# Sheet1.net
KiCad netlist of a schematic drawn in Altium Designer
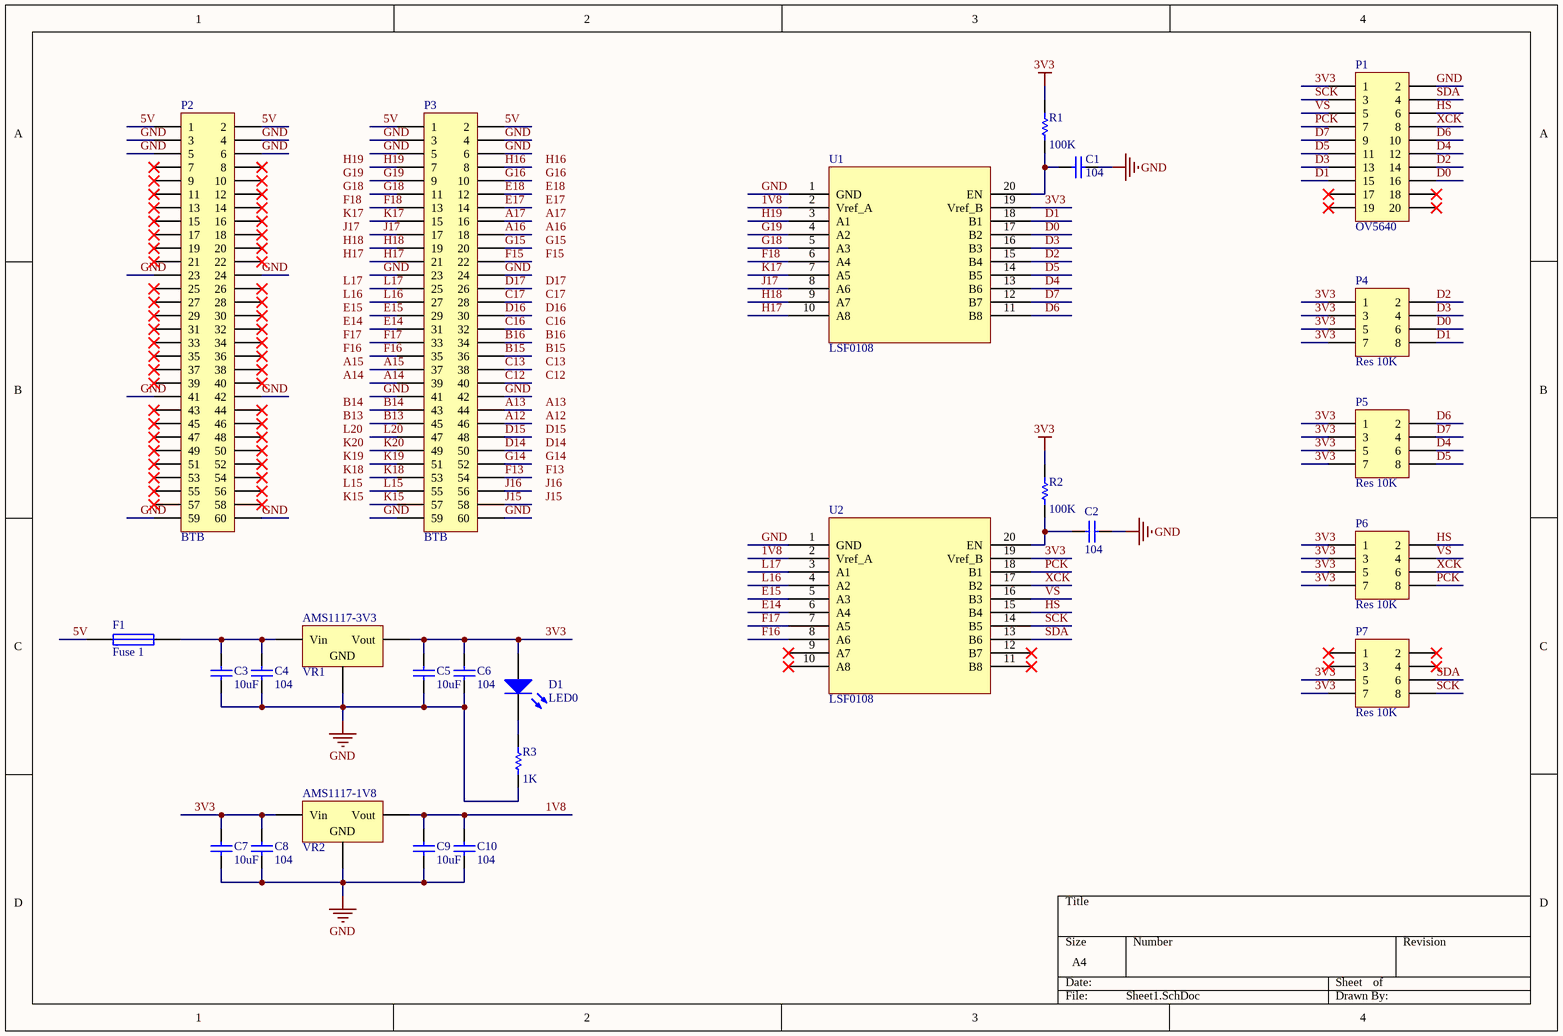
[diagram p0: Sheet1.SchDoc]

(export (version "E")
  (design (tool "Eeschema 10.0.6"))
  (components
    (comp (ref "C1")
      (value "104")
      (footprint "R0805")
      (description "Capacitor")
      (fields (field (name "Comment") "Cap") (field (name "PUBLISHER") "Altium Limited"))
      (libsource (lib "Miscellaneous Devices") (part "Cap"))
    )
    (comp (ref "C2")
      (value "104")
      (footprint "R0805")
      (description "Capacitor")
      (fields (field (name "Comment") "Cap") (field (name "PUBLISHER") "Altium Limited"))
      (libsource (lib "Miscellaneous Devices") (part "Cap"))
    )
    (comp (ref "C3")
      (value "10uF")
      (footprint "R0805")
      (description "Capacitor")
      (fields (field (name "Comment") "Cap") (field (name "PUBLISHER") "Altium Limited"))
      (libsource (lib "Miscellaneous Devices") (part "Cap"))
    )
    (comp (ref "C4")
      (value "104")
      (footprint "R0805")
      (description "Capacitor")
      (fields (field (name "Comment") "Cap") (field (name "PUBLISHER") "Altium Limited"))
      (libsource (lib "Miscellaneous Devices") (part "Cap"))
    )
    (comp (ref "C5")
      (value "10uF")
      (footprint "R0805")
      (description "Capacitor")
      (fields (field (name "Comment") "Cap") (field (name "PUBLISHER") "Altium Limited"))
      (libsource (lib "Miscellaneous Devices") (part "Cap"))
    )
    (comp (ref "C6")
      (value "104")
      (footprint "R0805")
      (description "Capacitor")
      (fields (field (name "Comment") "Cap") (field (name "PUBLISHER") "Altium Limited"))
      (libsource (lib "Miscellaneous Devices") (part "Cap"))
    )
    (comp (ref "C7")
      (value "10uF")
      (footprint "R0805")
      (description "Capacitor")
      (fields (field (name "Comment") "Cap") (field (name "PUBLISHER") "Altium Limited"))
      (libsource (lib "Miscellaneous Devices") (part "Cap"))
    )
    (comp (ref "C8")
      (value "104")
      (footprint "R0805")
      (description "Capacitor")
      (fields (field (name "Comment") "Cap") (field (name "PUBLISHER") "Altium Limited"))
      (libsource (lib "Miscellaneous Devices") (part "Cap"))
    )
    (comp (ref "C9")
      (value "10uF")
      (footprint "R0805")
      (description "Capacitor")
      (fields (field (name "Comment") "Cap") (field (name "PUBLISHER") "Altium Limited"))
      (libsource (lib "Miscellaneous Devices") (part "Cap"))
    )
    (comp (ref "C10")
      (value "104")
      (footprint "R0805")
      (description "Capacitor")
      (fields (field (name "Comment") "Cap") (field (name "PUBLISHER") "Altium Limited"))
      (libsource (lib "Miscellaneous Devices") (part "Cap"))
    )
    (comp (ref "D1")
      (value "LED0")
      (footprint "LED0805红")
      (description "Typical INFRARED GaAs LED")
      (fields (field (name "PUBLISHER") "Altium Limited"))
      (libsource (lib "Miscellaneous Devices") (part "LED0"))
    )
    (comp (ref "F1")
      (value "Fuse 1")
      (footprint "R1206")
      (description "Fuse")
      (fields (field (name "PUBLISHER") "Altium Limited"))
      (libsource (lib "Miscellaneous Devices") (part "Fuse 1"))
    )
    (comp (ref "P1")
      (value "OV5640")
      (footprint "HDR2X10")
      (description "Header, 10-Pin, Dual row")
      (fields (field (name "PUBLISHER") "Altium Limited"))
      (libsource (lib "Miscellaneous Connectors") (part "Header 10X2"))
    )
    (comp (ref "P2")
      (value "BTB")
      (footprint "BTBCON_0.8mm_60P")
      (description "Header, 30-Pin, Dual row")
      (fields (field (name "PUBLISHER") "Altium Limited"))
      (libsource (lib "Miscellaneous Connectors") (part "Header 30X2"))
    )
    (comp (ref "P3")
      (value "BTB")
      (footprint "BTBCON_0.8mm_60P")
      (description "Header, 30-Pin, Dual row")
      (fields (field (name "PUBLISHER") "Altium Limited"))
      (libsource (lib "Miscellaneous Connectors") (part "Header 30X2"))
    )
    (comp (ref "P4")
      (value "Res 10K")
      (footprint "排阻(4位贴片)")
      (description "Header, 4-Pin, Dual row")
      (fields (field (name "PUBLISHER") "Altium Limited"))
      (libsource (lib "Miscellaneous Connectors") (part "Header 4X2"))
    )
    (comp (ref "P5")
      (value "Res 10K")
      (footprint "排阻(4位贴片)")
      (description "Header, 4-Pin, Dual row")
      (fields (field (name "PUBLISHER") "Altium Limited"))
      (libsource (lib "Miscellaneous Connectors") (part "Header 4X2"))
    )
    (comp (ref "P6")
      (value "Res 10K")
      (footprint "排阻(4位贴片)")
      (description "Header, 4-Pin, Dual row")
      (fields (field (name "PUBLISHER") "Altium Limited"))
      (libsource (lib "Miscellaneous Connectors") (part "Header 4X2"))
    )
    (comp (ref "P7")
      (value "Res 10K")
      (footprint "排阻(4位贴片)")
      (description "Header, 4-Pin, Dual row")
      (fields (field (name "PUBLISHER") "Altium Limited"))
      (libsource (lib "Miscellaneous Connectors") (part "Header 4X2"))
    )
    (comp (ref "R1")
      (value "100K")
      (footprint "R0805")
      (description "Semiconductor Resistor")
      (fields (field (name "Comment") "Res Semi") (field (name "PUBLISHER") "Altium Limited"))
      (libsource (lib "Miscellaneous Devices") (part "Res Semi"))
    )
    (comp (ref "R2")
      (value "100K")
      (footprint "R0805")
      (description "Semiconductor Resistor")
      (fields (field (name "Comment") "Res Semi") (field (name "PUBLISHER") "Altium Limited"))
      (libsource (lib "Miscellaneous Devices") (part "Res Semi"))
    )
    (comp (ref "R3")
      (value "1K")
      (footprint "R0805")
      (description "Resistor")
      (fields (field (name "Comment") "Res1") (field (name "PUBLISHER") "Altium Limited"))
      (libsource (lib "Miscellaneous Devices") (part "Res1"))
    )
    (comp (ref "U1")
      (value "LSF0108")
      (footprint "TSSOP20 74lvc245")
      (libsource (lib "LSF0108") (part "LSF0108"))
    )
    (comp (ref "U2")
      (value "LSF0108")
      (footprint "TSSOP20 74lvc245")
      (libsource (lib "LSF0108") (part "LSF0108"))
    )
    (comp (ref "VR1")
      (value "AMS1117-3V3")
      (footprint "SOT-223")
      (description "Voltage Regulator")
      (fields (field (name "PUBLISHER") "Altium Limited"))
      (libsource (lib "Miscellaneous Devices") (part "Volt Reg"))
    )
    (comp (ref "VR2")
      (value "AMS1117-1V8")
      (footprint "SOT-223")
      (description "Voltage Regulator")
      (fields (field (name "PUBLISHER") "Altium Limited"))
      (libsource (lib "Miscellaneous Devices") (part "Volt Reg"))
    )
  )
  (nets
    (net (code "1") (name "/1V8") (class "Default")
      (node (ref "C10") (pin "2") (pinfunction "2_2") (pintype "passive"))
      (node (ref "C9") (pin "2") (pinfunction "2_2") (pintype "passive"))
      (node (ref "U1") (pin "2") (pinfunction "Vref_A_2") (pintype "passive"))
      (node (ref "U2") (pin "2") (pinfunction "Vref_A_2") (pintype "passive"))
      (node (ref "VR2") (pin "2") (pinfunction "Vout_2") (pintype "passive"))
    )
    (net (code "2") (name "/5V") (class "Default")
      (node (ref "F1") (pin "1") (pinfunction "1_1") (pintype "passive"))
      (node (ref "P2") (pin "1") (pinfunction "1_1") (pintype "passive"))
      (node (ref "P2") (pin "2") (pinfunction "2_2") (pintype "passive"))
      (node (ref "P3") (pin "1") (pinfunction "1_1") (pintype "passive"))
      (node (ref "P3") (pin "2") (pinfunction "2_2") (pintype "passive"))
    )
    (net (code "3") (name "/A12") (class "Default")
      (node (ref "P3") (pin "46") (pinfunction "46_46") (pintype "passive"))
    )
    (net (code "4") (name "/A13") (class "Default")
      (node (ref "P3") (pin "44") (pinfunction "44_44") (pintype "passive"))
    )
    (net (code "5") (name "/A14") (class "Default")
      (node (ref "P3") (pin "39") (pinfunction "39_39") (pintype "passive"))
    )
    (net (code "6") (name "/A15") (class "Default")
      (node (ref "P3") (pin "37") (pinfunction "37_37") (pintype "passive"))
    )
    (net (code "7") (name "/A16") (class "Default")
      (node (ref "P3") (pin "18") (pinfunction "18_18") (pintype "passive"))
    )
    (net (code "8") (name "/A17") (class "Default")
      (node (ref "P3") (pin "16") (pinfunction "16_16") (pintype "passive"))
    )
    (net (code "9") (name "/B13") (class "Default")
      (node (ref "P3") (pin "45") (pinfunction "45_45") (pintype "passive"))
    )
    (net (code "10") (name "/B14") (class "Default")
      (node (ref "P3") (pin "43") (pinfunction "43_43") (pintype "passive"))
    )
    (net (code "11") (name "/B15") (class "Default")
      (node (ref "P3") (pin "36") (pinfunction "36_36") (pintype "passive"))
    )
    (net (code "12") (name "/B16") (class "Default")
      (node (ref "P3") (pin "34") (pinfunction "34_34") (pintype "passive"))
    )
    (net (code "13") (name "/C12") (class "Default")
      (node (ref "P3") (pin "40") (pinfunction "40_40") (pintype "passive"))
    )
    (net (code "14") (name "/C13") (class "Default")
      (node (ref "P3") (pin "38") (pinfunction "38_38") (pintype "passive"))
    )
    (net (code "15") (name "/C16") (class "Default")
      (node (ref "P3") (pin "32") (pinfunction "32_32") (pintype "passive"))
    )
    (net (code "16") (name "/C17") (class "Default")
      (node (ref "P3") (pin "28") (pinfunction "28_28") (pintype "passive"))
    )
    (net (code "17") (name "/D0") (class "Default")
      (node (ref "P1") (pin "16") (pinfunction "16_16") (pintype "passive"))
      (node (ref "P4") (pin "6") (pinfunction "6_6") (pintype "passive"))
      (node (ref "U1") (pin "17") (pinfunction "B2_17") (pintype "passive"))
    )
    (net (code "18") (name "/D1") (class "Default")
      (node (ref "P1") (pin "15") (pinfunction "15_15") (pintype "passive"))
      (node (ref "P4") (pin "8") (pinfunction "8_8") (pintype "passive"))
      (node (ref "U1") (pin "18") (pinfunction "B1_18") (pintype "passive"))
    )
    (net (code "19") (name "/D2") (class "Default")
      (node (ref "P1") (pin "14") (pinfunction "14_14") (pintype "passive"))
      (node (ref "P4") (pin "2") (pinfunction "2_2") (pintype "passive"))
      (node (ref "U1") (pin "15") (pinfunction "B4_15") (pintype "passive"))
    )
    (net (code "20") (name "/D3") (class "Default")
      (node (ref "P1") (pin "13") (pinfunction "13_13") (pintype "passive"))
      (node (ref "P4") (pin "4") (pinfunction "4_4") (pintype "passive"))
      (node (ref "U1") (pin "16") (pinfunction "B3_16") (pintype "passive"))
    )
    (net (code "21") (name "/D4") (class "Default")
      (node (ref "P1") (pin "12") (pinfunction "12_12") (pintype "passive"))
      (node (ref "P5") (pin "6") (pinfunction "6_6") (pintype "passive"))
      (node (ref "U1") (pin "13") (pinfunction "B6_13") (pintype "passive"))
    )
    (net (code "22") (name "/D5") (class "Default")
      (node (ref "P1") (pin "11") (pinfunction "11_11") (pintype "passive"))
      (node (ref "P5") (pin "8") (pinfunction "8_8") (pintype "passive"))
      (node (ref "U1") (pin "14") (pinfunction "B5_14") (pintype "passive"))
    )
    (net (code "23") (name "/D6") (class "Default")
      (node (ref "P1") (pin "10") (pinfunction "10_10") (pintype "passive"))
      (node (ref "P5") (pin "2") (pinfunction "2_2") (pintype "passive"))
      (node (ref "U1") (pin "11") (pinfunction "B8_11") (pintype "passive"))
    )
    (net (code "24") (name "/D7") (class "Default")
      (node (ref "P1") (pin "9") (pinfunction "9_9") (pintype "passive"))
      (node (ref "P5") (pin "4") (pinfunction "4_4") (pintype "passive"))
      (node (ref "U1") (pin "12") (pinfunction "B7_12") (pintype "passive"))
    )
    (net (code "25") (name "/D14") (class "Default")
      (node (ref "P3") (pin "50") (pinfunction "50_50") (pintype "passive"))
    )
    (net (code "26") (name "/D15") (class "Default")
      (node (ref "P3") (pin "48") (pinfunction "48_48") (pintype "passive"))
    )
    (net (code "27") (name "/D16") (class "Default")
      (node (ref "P3") (pin "30") (pinfunction "30_30") (pintype "passive"))
    )
    (net (code "28") (name "/D17") (class "Default")
      (node (ref "P3") (pin "26") (pinfunction "26_26") (pintype "passive"))
    )
    (net (code "29") (name "/E14") (class "Default")
      (node (ref "P3") (pin "31") (pinfunction "31_31") (pintype "passive"))
      (node (ref "U2") (pin "6") (pinfunction "A4_6") (pintype "passive"))
    )
    (net (code "30") (name "/E15") (class "Default")
      (node (ref "P3") (pin "29") (pinfunction "29_29") (pintype "passive"))
      (node (ref "U2") (pin "5") (pinfunction "A3_5") (pintype "passive"))
    )
    (net (code "31") (name "/E17") (class "Default")
      (node (ref "P3") (pin "14") (pinfunction "14_14") (pintype "passive"))
    )
    (net (code "32") (name "/E18") (class "Default")
      (node (ref "P3") (pin "12") (pinfunction "12_12") (pintype "passive"))
    )
    (net (code "33") (name "/F13") (class "Default")
      (node (ref "P3") (pin "54") (pinfunction "54_54") (pintype "passive"))
    )
    (net (code "34") (name "/F15") (class "Default")
      (node (ref "P3") (pin "22") (pinfunction "22_22") (pintype "passive"))
    )
    (net (code "35") (name "/F16") (class "Default")
      (node (ref "P3") (pin "35") (pinfunction "35_35") (pintype "passive"))
      (node (ref "U2") (pin "8") (pinfunction "A6_8") (pintype "passive"))
    )
    (net (code "36") (name "/F17") (class "Default")
      (node (ref "P3") (pin "33") (pinfunction "33_33") (pintype "passive"))
      (node (ref "U2") (pin "7") (pinfunction "A5_7") (pintype "passive"))
    )
    (net (code "37") (name "/F18") (class "Default")
      (node (ref "P3") (pin "13") (pinfunction "13_13") (pintype "passive"))
      (node (ref "U1") (pin "6") (pinfunction "A4_6") (pintype "passive"))
    )
    (net (code "38") (name "/G14") (class "Default")
      (node (ref "P3") (pin "52") (pinfunction "52_52") (pintype "passive"))
    )
    (net (code "39") (name "/G15") (class "Default")
      (node (ref "P3") (pin "20") (pinfunction "20_20") (pintype "passive"))
    )
    (net (code "40") (name "/G16") (class "Default")
      (node (ref "P3") (pin "10") (pinfunction "10_10") (pintype "passive"))
    )
    (net (code "41") (name "/G18") (class "Default")
      (node (ref "P3") (pin "11") (pinfunction "11_11") (pintype "passive"))
      (node (ref "U1") (pin "5") (pinfunction "A3_5") (pintype "passive"))
    )
    (net (code "42") (name "/G19") (class "Default")
      (node (ref "P3") (pin "9") (pinfunction "9_9") (pintype "passive"))
      (node (ref "U1") (pin "4") (pinfunction "A2_4") (pintype "passive"))
    )
    (net (code "43") (name "/H16") (class "Default")
      (node (ref "P3") (pin "8") (pinfunction "8_8") (pintype "passive"))
    )
    (net (code "44") (name "/H17") (class "Default")
      (node (ref "P3") (pin "21") (pinfunction "21_21") (pintype "passive"))
      (node (ref "U1") (pin "10") (pinfunction "A8_10") (pintype "passive"))
    )
    (net (code "45") (name "/H18") (class "Default")
      (node (ref "P3") (pin "19") (pinfunction "19_19") (pintype "passive"))
      (node (ref "U1") (pin "9") (pinfunction "A7_9") (pintype "passive"))
    )
    (net (code "46") (name "/H19") (class "Default")
      (node (ref "P3") (pin "7") (pinfunction "7_7") (pintype "passive"))
      (node (ref "U1") (pin "3") (pinfunction "A1_3") (pintype "passive"))
    )
    (net (code "47") (name "/HS") (class "Default")
      (node (ref "P1") (pin "6") (pinfunction "6_6") (pintype "passive"))
      (node (ref "P6") (pin "2") (pinfunction "2_2") (pintype "passive"))
      (node (ref "U2") (pin "15") (pinfunction "B4_15") (pintype "passive"))
    )
    (net (code "48") (name "/J15") (class "Default")
      (node (ref "P3") (pin "58") (pinfunction "58_58") (pintype "passive"))
    )
    (net (code "49") (name "/J16") (class "Default")
      (node (ref "P3") (pin "56") (pinfunction "56_56") (pintype "passive"))
    )
    (net (code "50") (name "/J17") (class "Default")
      (node (ref "P3") (pin "17") (pinfunction "17_17") (pintype "passive"))
      (node (ref "U1") (pin "8") (pinfunction "A6_8") (pintype "passive"))
    )
    (net (code "51") (name "/K15") (class "Default")
      (node (ref "P3") (pin "57") (pinfunction "57_57") (pintype "passive"))
    )
    (net (code "52") (name "/K17") (class "Default")
      (node (ref "P3") (pin "15") (pinfunction "15_15") (pintype "passive"))
      (node (ref "U1") (pin "7") (pinfunction "A5_7") (pintype "passive"))
    )
    (net (code "53") (name "/K18") (class "Default")
      (node (ref "P3") (pin "53") (pinfunction "53_53") (pintype "passive"))
    )
    (net (code "54") (name "/K19") (class "Default")
      (node (ref "P3") (pin "51") (pinfunction "51_51") (pintype "passive"))
    )
    (net (code "55") (name "/K20") (class "Default")
      (node (ref "P3") (pin "49") (pinfunction "49_49") (pintype "passive"))
    )
    (net (code "56") (name "/L15") (class "Default")
      (node (ref "P3") (pin "55") (pinfunction "55_55") (pintype "passive"))
    )
    (net (code "57") (name "/L16") (class "Default")
      (node (ref "P3") (pin "27") (pinfunction "27_27") (pintype "passive"))
      (node (ref "U2") (pin "4") (pinfunction "A2_4") (pintype "passive"))
    )
    (net (code "58") (name "/L17") (class "Default")
      (node (ref "P3") (pin "25") (pinfunction "25_25") (pintype "passive"))
      (node (ref "U2") (pin "3") (pinfunction "A1_3") (pintype "passive"))
    )
    (net (code "59") (name "/L20") (class "Default")
      (node (ref "P3") (pin "47") (pinfunction "47_47") (pintype "passive"))
    )
    (net (code "60") (name "/PCK") (class "Default")
      (node (ref "P1") (pin "7") (pinfunction "7_7") (pintype "passive"))
      (node (ref "P6") (pin "8") (pinfunction "8_8") (pintype "passive"))
      (node (ref "U2") (pin "18") (pinfunction "B1_18") (pintype "passive"))
    )
    (net (code "61") (name "/SCK") (class "Default")
      (node (ref "P1") (pin "3") (pinfunction "3_3") (pintype "passive"))
      (node (ref "P7") (pin "8") (pinfunction "8_8") (pintype "passive"))
      (node (ref "U2") (pin "14") (pinfunction "B5_14") (pintype "passive"))
    )
    (net (code "62") (name "/SDA") (class "Default")
      (node (ref "P1") (pin "4") (pinfunction "4_4") (pintype "passive"))
      (node (ref "P7") (pin "6") (pinfunction "6_6") (pintype "passive"))
      (node (ref "U2") (pin "13") (pinfunction "B6_13") (pintype "passive"))
    )
    (net (code "63") (name "/VS") (class "Default")
      (node (ref "P1") (pin "5") (pinfunction "5_5") (pintype "passive"))
      (node (ref "P6") (pin "4") (pinfunction "4_4") (pintype "passive"))
      (node (ref "U2") (pin "16") (pinfunction "B3_16") (pintype "passive"))
    )
    (net (code "64") (name "/XCK") (class "Default")
      (node (ref "P1") (pin "8") (pinfunction "8_8") (pintype "passive"))
      (node (ref "P6") (pin "6") (pinfunction "6_6") (pintype "passive"))
      (node (ref "U2") (pin "17") (pinfunction "B2_17") (pintype "passive"))
    )
    (net (code "65") (name "3V3") (class "Default")
      (node (ref "C5") (pin "2") (pinfunction "2_2") (pintype "passive"))
      (node (ref "C6") (pin "2") (pinfunction "2_2") (pintype "passive"))
      (node (ref "C7") (pin "2") (pinfunction "2_2") (pintype "passive"))
      (node (ref "C8") (pin "2") (pinfunction "2_2") (pintype "passive"))
      (node (ref "D1") (pin "1") (pinfunction "A_1") (pintype "passive"))
      (node (ref "P1") (pin "1") (pinfunction "1_1") (pintype "passive"))
      (node (ref "P4") (pin "1") (pinfunction "1_1") (pintype "passive"))
      (node (ref "P4") (pin "3") (pinfunction "3_3") (pintype "passive"))
      (node (ref "P4") (pin "5") (pinfunction "5_5") (pintype "passive"))
      (node (ref "P4") (pin "7") (pinfunction "7_7") (pintype "passive"))
      (node (ref "P5") (pin "1") (pinfunction "1_1") (pintype "passive"))
      (node (ref "P5") (pin "3") (pinfunction "3_3") (pintype "passive"))
      (node (ref "P5") (pin "5") (pinfunction "5_5") (pintype "passive"))
      (node (ref "P5") (pin "7") (pinfunction "7_7") (pintype "passive"))
      (node (ref "P6") (pin "1") (pinfunction "1_1") (pintype "passive"))
      (node (ref "P6") (pin "3") (pinfunction "3_3") (pintype "passive"))
      (node (ref "P6") (pin "5") (pinfunction "5_5") (pintype "passive"))
      (node (ref "P6") (pin "7") (pinfunction "7_7") (pintype "passive"))
      (node (ref "P7") (pin "5") (pinfunction "5_5") (pintype "passive"))
      (node (ref "P7") (pin "7") (pinfunction "7_7") (pintype "passive"))
      (node (ref "R1") (pin "2") (pinfunction "2_2") (pintype "passive"))
      (node (ref "R2") (pin "2") (pinfunction "2_2") (pintype "passive"))
      (node (ref "U1") (pin "19") (pinfunction "Vref_B_19") (pintype "passive"))
      (node (ref "U2") (pin "19") (pinfunction "Vref_B_19") (pintype "passive"))
      (node (ref "VR1") (pin "2") (pinfunction "Vout_2") (pintype "passive"))
      (node (ref "VR2") (pin "3") (pinfunction "Vin_3") (pintype "passive"))
    )
    (net (code "66") (name "GND") (class "Default")
      (node (ref "C1") (pin "2") (pinfunction "2_2") (pintype "passive"))
      (node (ref "C10") (pin "1") (pinfunction "1_1") (pintype "passive"))
      (node (ref "C2") (pin "1") (pinfunction "1_1") (pintype "passive"))
      (node (ref "C3") (pin "1") (pinfunction "1_1") (pintype "passive"))
      (node (ref "C4") (pin "1") (pinfunction "1_1") (pintype "passive"))
      (node (ref "C5") (pin "1") (pinfunction "1_1") (pintype "passive"))
      (node (ref "C6") (pin "1") (pinfunction "1_1") (pintype "passive"))
      (node (ref "C7") (pin "1") (pinfunction "1_1") (pintype "passive"))
      (node (ref "C8") (pin "1") (pinfunction "1_1") (pintype "passive"))
      (node (ref "C9") (pin "1") (pinfunction "1_1") (pintype "passive"))
      (node (ref "P1") (pin "2") (pinfunction "2_2") (pintype "passive"))
      (node (ref "P2") (pin "23") (pinfunction "23_23") (pintype "passive"))
      (node (ref "P2") (pin "24") (pinfunction "24_24") (pintype "passive"))
      (node (ref "P2") (pin "3") (pinfunction "3_3") (pintype "passive"))
      (node (ref "P2") (pin "4") (pinfunction "4_4") (pintype "passive"))
      (node (ref "P2") (pin "41") (pinfunction "41_41") (pintype "passive"))
      (node (ref "P2") (pin "42") (pinfunction "42_42") (pintype "passive"))
      (node (ref "P2") (pin "5") (pinfunction "5_5") (pintype "passive"))
      (node (ref "P2") (pin "59") (pinfunction "59_59") (pintype "passive"))
      (node (ref "P2") (pin "6") (pinfunction "6_6") (pintype "passive"))
      (node (ref "P2") (pin "60") (pinfunction "60_60") (pintype "passive"))
      (node (ref "P3") (pin "23") (pinfunction "23_23") (pintype "passive"))
      (node (ref "P3") (pin "24") (pinfunction "24_24") (pintype "passive"))
      (node (ref "P3") (pin "3") (pinfunction "3_3") (pintype "passive"))
      (node (ref "P3") (pin "4") (pinfunction "4_4") (pintype "passive"))
      (node (ref "P3") (pin "41") (pinfunction "41_41") (pintype "passive"))
      (node (ref "P3") (pin "42") (pinfunction "42_42") (pintype "passive"))
      (node (ref "P3") (pin "5") (pinfunction "5_5") (pintype "passive"))
      (node (ref "P3") (pin "59") (pinfunction "59_59") (pintype "passive"))
      (node (ref "P3") (pin "6") (pinfunction "6_6") (pintype "passive"))
      (node (ref "P3") (pin "60") (pinfunction "60_60") (pintype "passive"))
      (node (ref "R3") (pin "1") (pinfunction "1_1") (pintype "passive"))
      (node (ref "U1") (pin "1") (pinfunction "GND_1") (pintype "passive"))
      (node (ref "U2") (pin "1") (pinfunction "GND_1") (pintype "passive"))
      (node (ref "VR1") (pin "1") (pinfunction "GND_1") (pintype "passive"))
      (node (ref "VR2") (pin "1") (pinfunction "GND_1") (pintype "passive"))
    )
    (net (code "67") (name "Net-(D1-K)") (class "Default")
      (node (ref "D1") (pin "2") (pinfunction "K_2") (pintype "passive"))
      (node (ref "R3") (pin "2") (pinfunction "2_2") (pintype "passive"))
    )
    (net (code "68") (name "Net-(U1-EN)") (class "Default")
      (node (ref "C1") (pin "1") (pinfunction "1_1") (pintype "passive"))
      (node (ref "R1") (pin "1") (pinfunction "1_1") (pintype "passive"))
      (node (ref "U1") (pin "20") (pinfunction "EN_20") (pintype "passive"))
    )
    (net (code "69") (name "Net-(U2-EN)") (class "Default")
      (node (ref "C2") (pin "2") (pinfunction "2_2") (pintype "passive"))
      (node (ref "R2") (pin "1") (pinfunction "1_1") (pintype "passive"))
      (node (ref "U2") (pin "20") (pinfunction "EN_20") (pintype "passive"))
    )
    (net (code "70") (name "Net-(VR1-Vin)") (class "Default")
      (node (ref "C3") (pin "2") (pinfunction "2_2") (pintype "passive"))
      (node (ref "C4") (pin "2") (pinfunction "2_2") (pintype "passive"))
      (node (ref "F1") (pin "2") (pinfunction "2_2") (pintype "passive"))
      (node (ref "VR1") (pin "3") (pinfunction "Vin_3") (pintype "passive"))
    )
    (net (code "71") (name "unconnected-(P1-Pad17)") (class "Default")
      (node (ref "P1") (pin "17") (pinfunction "17_17") (pintype "passive+no_connect"))
    )
    (net (code "72") (name "unconnected-(P1-Pad18)") (class "Default")
      (node (ref "P1") (pin "18") (pinfunction "18_18") (pintype "passive+no_connect"))
    )
    (net (code "73") (name "unconnected-(P1-Pad19)") (class "Default")
      (node (ref "P1") (pin "19") (pinfunction "19_19") (pintype "passive+no_connect"))
    )
    (net (code "74") (name "unconnected-(P1-Pad20)") (class "Default")
      (node (ref "P1") (pin "20") (pinfunction "20_20") (pintype "passive+no_connect"))
    )
    (net (code "75") (name "unconnected-(P2-Pad7)") (class "Default")
      (node (ref "P2") (pin "7") (pinfunction "7_7") (pintype "passive+no_connect"))
    )
    (net (code "76") (name "unconnected-(P2-Pad8)") (class "Default")
      (node (ref "P2") (pin "8") (pinfunction "8_8") (pintype "passive+no_connect"))
    )
    (net (code "77") (name "unconnected-(P2-Pad9)") (class "Default")
      (node (ref "P2") (pin "9") (pinfunction "9_9") (pintype "passive+no_connect"))
    )
    (net (code "78") (name "unconnected-(P2-Pad10)") (class "Default")
      (node (ref "P2") (pin "10") (pinfunction "10_10") (pintype "passive+no_connect"))
    )
    (net (code "79") (name "unconnected-(P2-Pad11)") (class "Default")
      (node (ref "P2") (pin "11") (pinfunction "11_11") (pintype "passive+no_connect"))
    )
    (net (code "80") (name "unconnected-(P2-Pad12)") (class "Default")
      (node (ref "P2") (pin "12") (pinfunction "12_12") (pintype "passive+no_connect"))
    )
    (net (code "81") (name "unconnected-(P2-Pad13)") (class "Default")
      (node (ref "P2") (pin "13") (pinfunction "13_13") (pintype "passive+no_connect"))
    )
    (net (code "82") (name "unconnected-(P2-Pad14)") (class "Default")
      (node (ref "P2") (pin "14") (pinfunction "14_14") (pintype "passive+no_connect"))
    )
    (net (code "83") (name "unconnected-(P2-Pad15)") (class "Default")
      (node (ref "P2") (pin "15") (pinfunction "15_15") (pintype "passive+no_connect"))
    )
    (net (code "84") (name "unconnected-(P2-Pad16)") (class "Default")
      (node (ref "P2") (pin "16") (pinfunction "16_16") (pintype "passive+no_connect"))
    )
    (net (code "85") (name "unconnected-(P2-Pad17)") (class "Default")
      (node (ref "P2") (pin "17") (pinfunction "17_17") (pintype "passive+no_connect"))
    )
    (net (code "86") (name "unconnected-(P2-Pad18)") (class "Default")
      (node (ref "P2") (pin "18") (pinfunction "18_18") (pintype "passive+no_connect"))
    )
    (net (code "87") (name "unconnected-(P2-Pad19)") (class "Default")
      (node (ref "P2") (pin "19") (pinfunction "19_19") (pintype "passive+no_connect"))
    )
    (net (code "88") (name "unconnected-(P2-Pad20)") (class "Default")
      (node (ref "P2") (pin "20") (pinfunction "20_20") (pintype "passive+no_connect"))
    )
    (net (code "89") (name "unconnected-(P2-Pad21)") (class "Default")
      (node (ref "P2") (pin "21") (pinfunction "21_21") (pintype "passive+no_connect"))
    )
    (net (code "90") (name "unconnected-(P2-Pad22)") (class "Default")
      (node (ref "P2") (pin "22") (pinfunction "22_22") (pintype "passive+no_connect"))
    )
    (net (code "91") (name "unconnected-(P2-Pad25)") (class "Default")
      (node (ref "P2") (pin "25") (pinfunction "25_25") (pintype "passive+no_connect"))
    )
    (net (code "92") (name "unconnected-(P2-Pad26)") (class "Default")
      (node (ref "P2") (pin "26") (pinfunction "26_26") (pintype "passive+no_connect"))
    )
    (net (code "93") (name "unconnected-(P2-Pad27)") (class "Default")
      (node (ref "P2") (pin "27") (pinfunction "27_27") (pintype "passive+no_connect"))
    )
    (net (code "94") (name "unconnected-(P2-Pad28)") (class "Default")
      (node (ref "P2") (pin "28") (pinfunction "28_28") (pintype "passive+no_connect"))
    )
    (net (code "95") (name "unconnected-(P2-Pad29)") (class "Default")
      (node (ref "P2") (pin "29") (pinfunction "29_29") (pintype "passive+no_connect"))
    )
    (net (code "96") (name "unconnected-(P2-Pad30)") (class "Default")
      (node (ref "P2") (pin "30") (pinfunction "30_30") (pintype "passive+no_connect"))
    )
    (net (code "97") (name "unconnected-(P2-Pad31)") (class "Default")
      (node (ref "P2") (pin "31") (pinfunction "31_31") (pintype "passive+no_connect"))
    )
    (net (code "98") (name "unconnected-(P2-Pad32)") (class "Default")
      (node (ref "P2") (pin "32") (pinfunction "32_32") (pintype "passive+no_connect"))
    )
    (net (code "99") (name "unconnected-(P2-Pad33)") (class "Default")
      (node (ref "P2") (pin "33") (pinfunction "33_33") (pintype "passive+no_connect"))
    )
    (net (code "100") (name "unconnected-(P2-Pad34)") (class "Default")
      (node (ref "P2") (pin "34") (pinfunction "34_34") (pintype "passive+no_connect"))
    )
    (net (code "101") (name "unconnected-(P2-Pad35)") (class "Default")
      (node (ref "P2") (pin "35") (pinfunction "35_35") (pintype "passive+no_connect"))
    )
    (net (code "102") (name "unconnected-(P2-Pad36)") (class "Default")
      (node (ref "P2") (pin "36") (pinfunction "36_36") (pintype "passive+no_connect"))
    )
    (net (code "103") (name "unconnected-(P2-Pad37)") (class "Default")
      (node (ref "P2") (pin "37") (pinfunction "37_37") (pintype "passive+no_connect"))
    )
    (net (code "104") (name "unconnected-(P2-Pad38)") (class "Default")
      (node (ref "P2") (pin "38") (pinfunction "38_38") (pintype "passive+no_connect"))
    )
    (net (code "105") (name "unconnected-(P2-Pad39)") (class "Default")
      (node (ref "P2") (pin "39") (pinfunction "39_39") (pintype "passive+no_connect"))
    )
    (net (code "106") (name "unconnected-(P2-Pad40)") (class "Default")
      (node (ref "P2") (pin "40") (pinfunction "40_40") (pintype "passive+no_connect"))
    )
    (net (code "107") (name "unconnected-(P2-Pad43)") (class "Default")
      (node (ref "P2") (pin "43") (pinfunction "43_43") (pintype "passive+no_connect"))
    )
    (net (code "108") (name "unconnected-(P2-Pad44)") (class "Default")
      (node (ref "P2") (pin "44") (pinfunction "44_44") (pintype "passive+no_connect"))
    )
    (net (code "109") (name "unconnected-(P2-Pad45)") (class "Default")
      (node (ref "P2") (pin "45") (pinfunction "45_45") (pintype "passive+no_connect"))
    )
    (net (code "110") (name "unconnected-(P2-Pad46)") (class "Default")
      (node (ref "P2") (pin "46") (pinfunction "46_46") (pintype "passive+no_connect"))
    )
    (net (code "111") (name "unconnected-(P2-Pad47)") (class "Default")
      (node (ref "P2") (pin "47") (pinfunction "47_47") (pintype "passive+no_connect"))
    )
    (net (code "112") (name "unconnected-(P2-Pad48)") (class "Default")
      (node (ref "P2") (pin "48") (pinfunction "48_48") (pintype "passive+no_connect"))
    )
    (net (code "113") (name "unconnected-(P2-Pad49)") (class "Default")
      (node (ref "P2") (pin "49") (pinfunction "49_49") (pintype "passive+no_connect"))
    )
    (net (code "114") (name "unconnected-(P2-Pad50)") (class "Default")
      (node (ref "P2") (pin "50") (pinfunction "50_50") (pintype "passive+no_connect"))
    )
    (net (code "115") (name "unconnected-(P2-Pad51)") (class "Default")
      (node (ref "P2") (pin "51") (pinfunction "51_51") (pintype "passive+no_connect"))
    )
    (net (code "116") (name "unconnected-(P2-Pad52)") (class "Default")
      (node (ref "P2") (pin "52") (pinfunction "52_52") (pintype "passive+no_connect"))
    )
    (net (code "117") (name "unconnected-(P2-Pad53)") (class "Default")
      (node (ref "P2") (pin "53") (pinfunction "53_53") (pintype "passive+no_connect"))
    )
    (net (code "118") (name "unconnected-(P2-Pad54)") (class "Default")
      (node (ref "P2") (pin "54") (pinfunction "54_54") (pintype "passive+no_connect"))
    )
    (net (code "119") (name "unconnected-(P2-Pad55)") (class "Default")
      (node (ref "P2") (pin "55") (pinfunction "55_55") (pintype "passive+no_connect"))
    )
    (net (code "120") (name "unconnected-(P2-Pad56)") (class "Default")
      (node (ref "P2") (pin "56") (pinfunction "56_56") (pintype "passive+no_connect"))
    )
    (net (code "121") (name "unconnected-(P2-Pad57)") (class "Default")
      (node (ref "P2") (pin "57") (pinfunction "57_57") (pintype "passive+no_connect"))
    )
    (net (code "122") (name "unconnected-(P2-Pad58)") (class "Default")
      (node (ref "P2") (pin "58") (pinfunction "58_58") (pintype "passive+no_connect"))
    )
    (net (code "123") (name "unconnected-(P7-Pad1)") (class "Default")
      (node (ref "P7") (pin "1") (pinfunction "1_1") (pintype "passive+no_connect"))
    )
    (net (code "124") (name "unconnected-(P7-Pad2)") (class "Default")
      (node (ref "P7") (pin "2") (pinfunction "2_2") (pintype "passive+no_connect"))
    )
    (net (code "125") (name "unconnected-(P7-Pad3)") (class "Default")
      (node (ref "P7") (pin "3") (pinfunction "3_3") (pintype "passive+no_connect"))
    )
    (net (code "126") (name "unconnected-(P7-Pad4)") (class "Default")
      (node (ref "P7") (pin "4") (pinfunction "4_4") (pintype "passive+no_connect"))
    )
    (net (code "127") (name "unconnected-(U2-A7-Pad9)") (class "Default")
      (node (ref "U2") (pin "9") (pinfunction "A7_9") (pintype "passive+no_connect"))
    )
    (net (code "128") (name "unconnected-(U2-A8-Pad10)") (class "Default")
      (node (ref "U2") (pin "10") (pinfunction "A8_10") (pintype "passive+no_connect"))
    )
    (net (code "129") (name "unconnected-(U2-B7-Pad12)") (class "Default")
      (node (ref "U2") (pin "12") (pinfunction "B7_12") (pintype "passive+no_connect"))
    )
    (net (code "130") (name "unconnected-(U2-B8-Pad11)") (class "Default")
      (node (ref "U2") (pin "11") (pinfunction "B8_11") (pintype "passive+no_connect"))
    )
  )
)
